# komparator.net
KiCad netlist of a schematic drawn in EAGLE
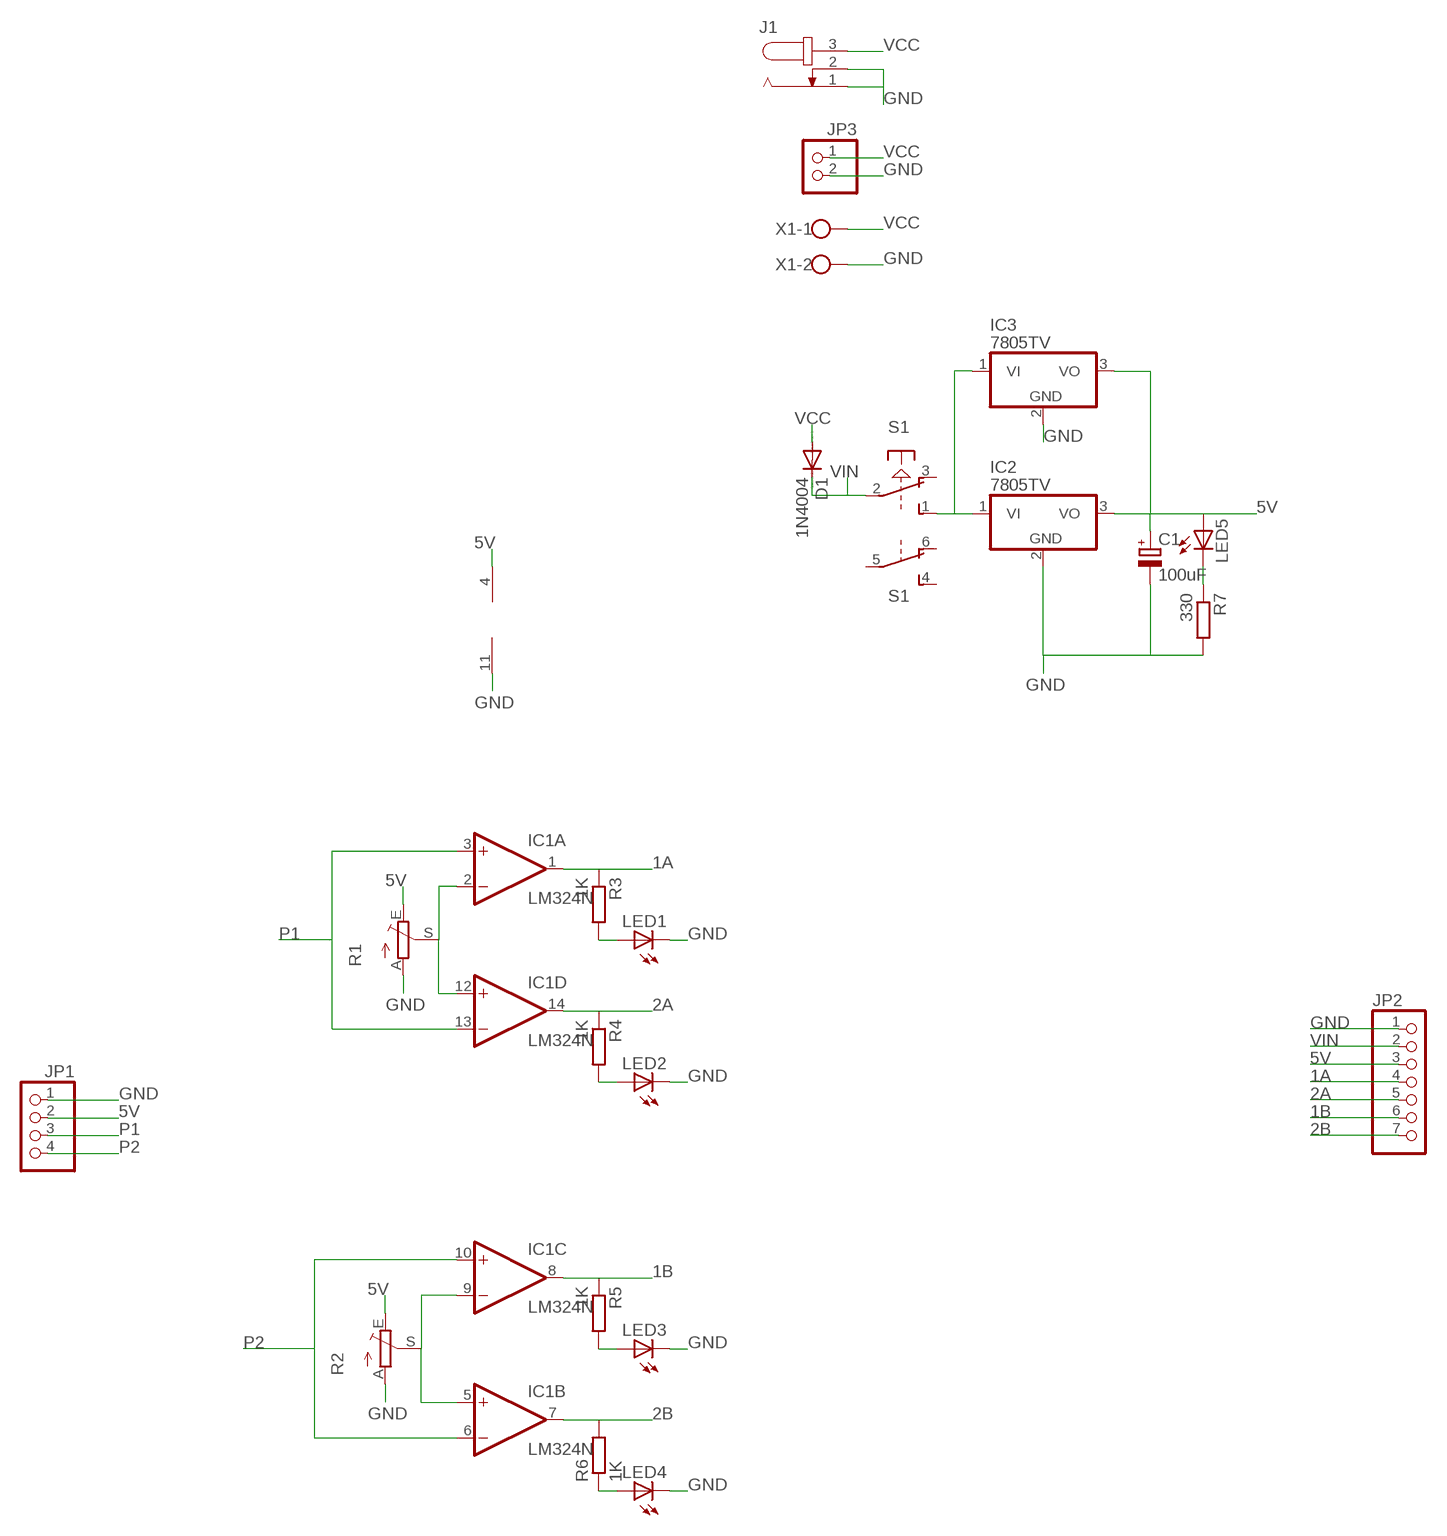
[diagram p0: schematic, sheet 1]

(export (version "E")
  (design (tool "Eeschema 10.0.6"))
  (components
    (comp (ref "C1")
      (value "100uF")
      (footprint "eagle-import:E2,5-6")
      (libsource (lib "eagle-import") (part "CPOL-EUE2.5-6"))
    )
    (comp (ref "D1")
      (value "1N4004")
      (footprint "eagle-import:DO41-10")
      (libsource (lib "eagle-import") (part "1N4004"))
    )
    (comp (ref "IC1")
      (value "LM324N")
      (footprint "eagle-import:DIL14")
      (libsource (lib "eagle-import") (part "LM324N"))
    )
    (comp (ref "IC2")
      (value "7805TV")
      (footprint "eagle-import:TO220V")
      (libsource (lib "eagle-import") (part "78TV05"))
    )
    (comp (ref "IC3")
      (value "7805TV")
      (footprint "eagle-import:TO220V")
      (libsource (lib "eagle-import") (part "78TV05"))
    )
    (comp (ref "J1")
      (value "JACK-PLUG0")
      (footprint "eagle-import:SPC4077")
      (libsource (lib "eagle-import") (part "JACK-PLUG0"))
    )
    (comp (ref "JP1")
      (value "PINHD-1X4")
      (footprint "eagle-import:1X04")
      (libsource (lib "eagle-import") (part "PINHD-1X4"))
    )
    (comp (ref "JP2")
      (value "PINHD-1X7")
      (footprint "eagle-import:1X07")
      (libsource (lib "eagle-import") (part "PINHD-1X7"))
    )
    (comp (ref "JP3")
      (value "PINHD-1X2")
      (footprint "eagle-import:1X02")
      (libsource (lib "eagle-import") (part "PINHD-1X2"))
    )
    (comp (ref "LED1")
      (value "LED3MM")
      (footprint "eagle-import:LED3MM")
      (libsource (lib "eagle-import") (part "LED3MM"))
    )
    (comp (ref "LED2")
      (value "LED3MM")
      (footprint "eagle-import:LED3MM")
      (libsource (lib "eagle-import") (part "LED3MM"))
    )
    (comp (ref "LED3")
      (value "LED3MM")
      (footprint "eagle-import:LED3MM")
      (libsource (lib "eagle-import") (part "LED3MM"))
    )
    (comp (ref "LED4")
      (value "LED3MM")
      (footprint "eagle-import:LED3MM")
      (libsource (lib "eagle-import") (part "LED3MM"))
    )
    (comp (ref "LED5")
      (value "LED3MM")
      (footprint "eagle-import:LED3MM")
      (libsource (lib "eagle-import") (part "LED3MM"))
    )
    (comp (ref "R1")
      (value "TRIM_EU-CA6V")
      (footprint "eagle-import:CA6V")
      (libsource (lib "eagle-import") (part "TRIM_EU-CA6V"))
    )
    (comp (ref "R2")
      (value "TRIM_EU-CA6V")
      (footprint "eagle-import:CA6V")
      (libsource (lib "eagle-import") (part "TRIM_EU-CA6V"))
    )
    (comp (ref "R3")
      (value "1K")
      (footprint "eagle-import:0207_7")
      (libsource (lib "eagle-import") (part "R-EU_0207/7"))
    )
    (comp (ref "R4")
      (value "1K")
      (footprint "eagle-import:0207_7")
      (libsource (lib "eagle-import") (part "R-EU_0207/7"))
    )
    (comp (ref "R5")
      (value "1K")
      (footprint "eagle-import:0207_7")
      (libsource (lib "eagle-import") (part "R-EU_0207/7"))
    )
    (comp (ref "R6")
      (value "1K")
      (footprint "eagle-import:0207_7")
      (libsource (lib "eagle-import") (part "R-EU_0207/7"))
    )
    (comp (ref "R7")
      (value "330")
      (footprint "eagle-import:0207_7")
      (libsource (lib "eagle-import") (part "R-EU_0207/7"))
    )
    (comp (ref "S1")
      (value "PVA2R")
      (footprint "eagle-import:PVA2R")
      (libsource (lib "eagle-import") (part "PVA2R"))
    )
    (comp (ref "X1")
      (value "W237-102")
      (footprint "eagle-import:W237-102")
      (fields (field (name "MPN") "237-102"))
      (libsource (lib "eagle-import") (part "W237-102"))
    )
  )
  (nets
    (net (code "1") (name "/1A") (class "Default")
      (node (ref "IC1") (pin "1") (pinfunction "OUT_1") (pintype "output"))
      (node (ref "JP2") (pin "4") (pinfunction "4_4") (pintype "passive"))
      (node (ref "R3") (pin "1") (pinfunction "1_1") (pintype "passive"))
    )
    (net (code "2") (name "/1B") (class "Default")
      (node (ref "IC1") (pin "8") (pinfunction "OUT_8") (pintype "output"))
      (node (ref "JP2") (pin "6") (pinfunction "6_6") (pintype "passive"))
      (node (ref "R5") (pin "1") (pinfunction "1_1") (pintype "passive"))
    )
    (net (code "3") (name "/2A") (class "Default")
      (node (ref "IC1") (pin "14") (pinfunction "OUT_14") (pintype "output"))
      (node (ref "JP2") (pin "5") (pinfunction "5_5") (pintype "passive"))
      (node (ref "R4") (pin "1") (pinfunction "1_1") (pintype "passive"))
    )
    (net (code "4") (name "/2B") (class "Default")
      (node (ref "IC1") (pin "7") (pinfunction "OUT_7") (pintype "output"))
      (node (ref "JP2") (pin "7") (pinfunction "7_7") (pintype "passive"))
      (node (ref "R6") (pin "2") (pinfunction "2_2") (pintype "passive"))
    )
    (net (code "5") (name "/5V") (class "Default")
      (node (ref "C1") (pin "+") (pinfunction "+_+") (pintype "passive"))
      (node (ref "IC1") (pin "4") (pinfunction "V+_4") (pintype "power_in"))
      (node (ref "IC2") (pin "3") (pinfunction "VO_3") (pintype "passive"))
      (node (ref "IC3") (pin "3") (pinfunction "VO_3") (pintype "passive"))
      (node (ref "JP1") (pin "2") (pinfunction "2_2") (pintype "passive"))
      (node (ref "JP2") (pin "3") (pinfunction "3_3") (pintype "passive"))
      (node (ref "LED5") (pin "A") (pinfunction "A_A") (pintype "passive"))
      (node (ref "R1") (pin "E") (pinfunction "E_E") (pintype "passive"))
      (node (ref "R2") (pin "E") (pinfunction "E_E") (pintype "passive"))
    )
    (net (code "6") (name "/GND") (class "Default")
      (node (ref "C1") (pin "-") (pinfunction "-_-") (pintype "passive"))
      (node (ref "IC1") (pin "11") (pinfunction "V-_11") (pintype "power_in"))
      (node (ref "IC2") (pin "2") (pinfunction "GND_2") (pintype "passive"))
      (node (ref "IC3") (pin "2") (pinfunction "GND_2") (pintype "passive"))
      (node (ref "J1") (pin "1") (pinfunction "1_1") (pintype "passive"))
      (node (ref "J1") (pin "2") (pinfunction "2_2") (pintype "passive"))
      (node (ref "JP1") (pin "1") (pinfunction "1_1") (pintype "passive"))
      (node (ref "JP2") (pin "1") (pinfunction "1_1") (pintype "passive"))
      (node (ref "JP3") (pin "2") (pinfunction "2_2") (pintype "passive"))
      (node (ref "LED1") (pin "K") (pinfunction "C_K") (pintype "passive"))
      (node (ref "LED2") (pin "K") (pinfunction "C_K") (pintype "passive"))
      (node (ref "LED3") (pin "K") (pinfunction "C_K") (pintype "passive"))
      (node (ref "LED4") (pin "K") (pinfunction "C_K") (pintype "passive"))
      (node (ref "R1") (pin "A") (pinfunction "A_A") (pintype "passive"))
      (node (ref "R2") (pin "A") (pinfunction "A_A") (pintype "passive"))
      (node (ref "R7") (pin "2") (pinfunction "2_2") (pintype "passive"))
      (node (ref "X1") (pin "2") (pinfunction "KL_2") (pintype "passive"))
    )
    (net (code "7") (name "/P1") (class "Default")
      (node (ref "IC1") (pin "13") (pinfunction "-IN_13") (pintype "input"))
      (node (ref "IC1") (pin "3") (pinfunction "+IN_3") (pintype "input"))
      (node (ref "JP1") (pin "3") (pinfunction "3_3") (pintype "passive"))
    )
    (net (code "8") (name "/P2") (class "Default")
      (node (ref "IC1") (pin "10") (pinfunction "+IN_10") (pintype "input"))
      (node (ref "IC1") (pin "6") (pinfunction "-IN_6") (pintype "input"))
      (node (ref "JP1") (pin "4") (pinfunction "4_4") (pintype "passive"))
    )
    (net (code "9") (name "/VCC") (class "Default")
      (node (ref "D1") (pin "A") (pinfunction "A_A") (pintype "passive"))
      (node (ref "J1") (pin "3") (pinfunction "3_3") (pintype "passive"))
      (node (ref "JP3") (pin "1") (pinfunction "1_1") (pintype "passive"))
      (node (ref "X1") (pin "1") (pinfunction "KL_1") (pintype "passive"))
    )
    (net (code "10") (name "/VIN") (class "Default")
      (node (ref "D1") (pin "C") (pinfunction "C_C") (pintype "passive"))
      (node (ref "JP2") (pin "2") (pinfunction "2_2") (pintype "passive"))
      (node (ref "S1") (pin "2") (pinfunction "P_2") (pintype "passive"))
    )
    (net (code "11") (name "Net-(IC1A--IN)") (class "Default")
      (node (ref "IC1") (pin "12") (pinfunction "+IN_12") (pintype "input"))
      (node (ref "IC1") (pin "2") (pinfunction "-IN_2") (pintype "input"))
      (node (ref "R1") (pin "S") (pinfunction "S_S") (pintype "passive"))
    )
    (net (code "12") (name "Net-(IC1B-+IN)") (class "Default")
      (node (ref "IC1") (pin "5") (pinfunction "+IN_5") (pintype "input"))
      (node (ref "IC1") (pin "9") (pinfunction "-IN_9") (pintype "input"))
      (node (ref "R2") (pin "S") (pinfunction "S_S") (pintype "passive"))
    )
    (net (code "13") (name "Net-(IC2-VI)") (class "Default")
      (node (ref "IC2") (pin "1") (pinfunction "VI_1") (pintype "input"))
      (node (ref "IC3") (pin "1") (pinfunction "VI_1") (pintype "input"))
      (node (ref "S1") (pin "1") (pinfunction "S_1") (pintype "passive"))
    )
    (net (code "14") (name "Net-(LED1-PadA)") (class "Default")
      (node (ref "LED1") (pin "A") (pinfunction "A_A") (pintype "passive"))
      (node (ref "R3") (pin "2") (pinfunction "2_2") (pintype "passive"))
    )
    (net (code "15") (name "Net-(LED2-PadA)") (class "Default")
      (node (ref "LED2") (pin "A") (pinfunction "A_A") (pintype "passive"))
      (node (ref "R4") (pin "2") (pinfunction "2_2") (pintype "passive"))
    )
    (net (code "16") (name "Net-(LED3-PadA)") (class "Default")
      (node (ref "LED3") (pin "A") (pinfunction "A_A") (pintype "passive"))
      (node (ref "R5") (pin "2") (pinfunction "2_2") (pintype "passive"))
    )
    (net (code "17") (name "Net-(LED4-PadA)") (class "Default")
      (node (ref "LED4") (pin "A") (pinfunction "A_A") (pintype "passive"))
      (node (ref "R6") (pin "1") (pinfunction "1_1") (pintype "passive"))
    )
    (net (code "18") (name "Net-(LED5-C)") (class "Default")
      (node (ref "LED5") (pin "K") (pinfunction "C_K") (pintype "passive"))
      (node (ref "R7") (pin "1") (pinfunction "1_1") (pintype "passive"))
    )
    (net (code "19") (name "unconnected-(S1A-O-Pad3)") (class "Default")
      (node (ref "S1") (pin "3") (pinfunction "O_3") (pintype "passive"))
    )
    (net (code "20") (name "unconnected-(S1B-O-Pad6)") (class "Default")
      (node (ref "S1") (pin "6") (pinfunction "O_6") (pintype "passive"))
    )
    (net (code "21") (name "unconnected-(S1B-P-Pad5)") (class "Default")
      (node (ref "S1") (pin "5") (pinfunction "P_5") (pintype "passive"))
    )
    (net (code "22") (name "unconnected-(S1B-S-Pad4)") (class "Default")
      (node (ref "S1") (pin "4") (pinfunction "S_4") (pintype "passive"))
    )
  )
)
